# G1Tech-BME680_r1.net
KiCad netlist of a schematic drawn in EAGLE
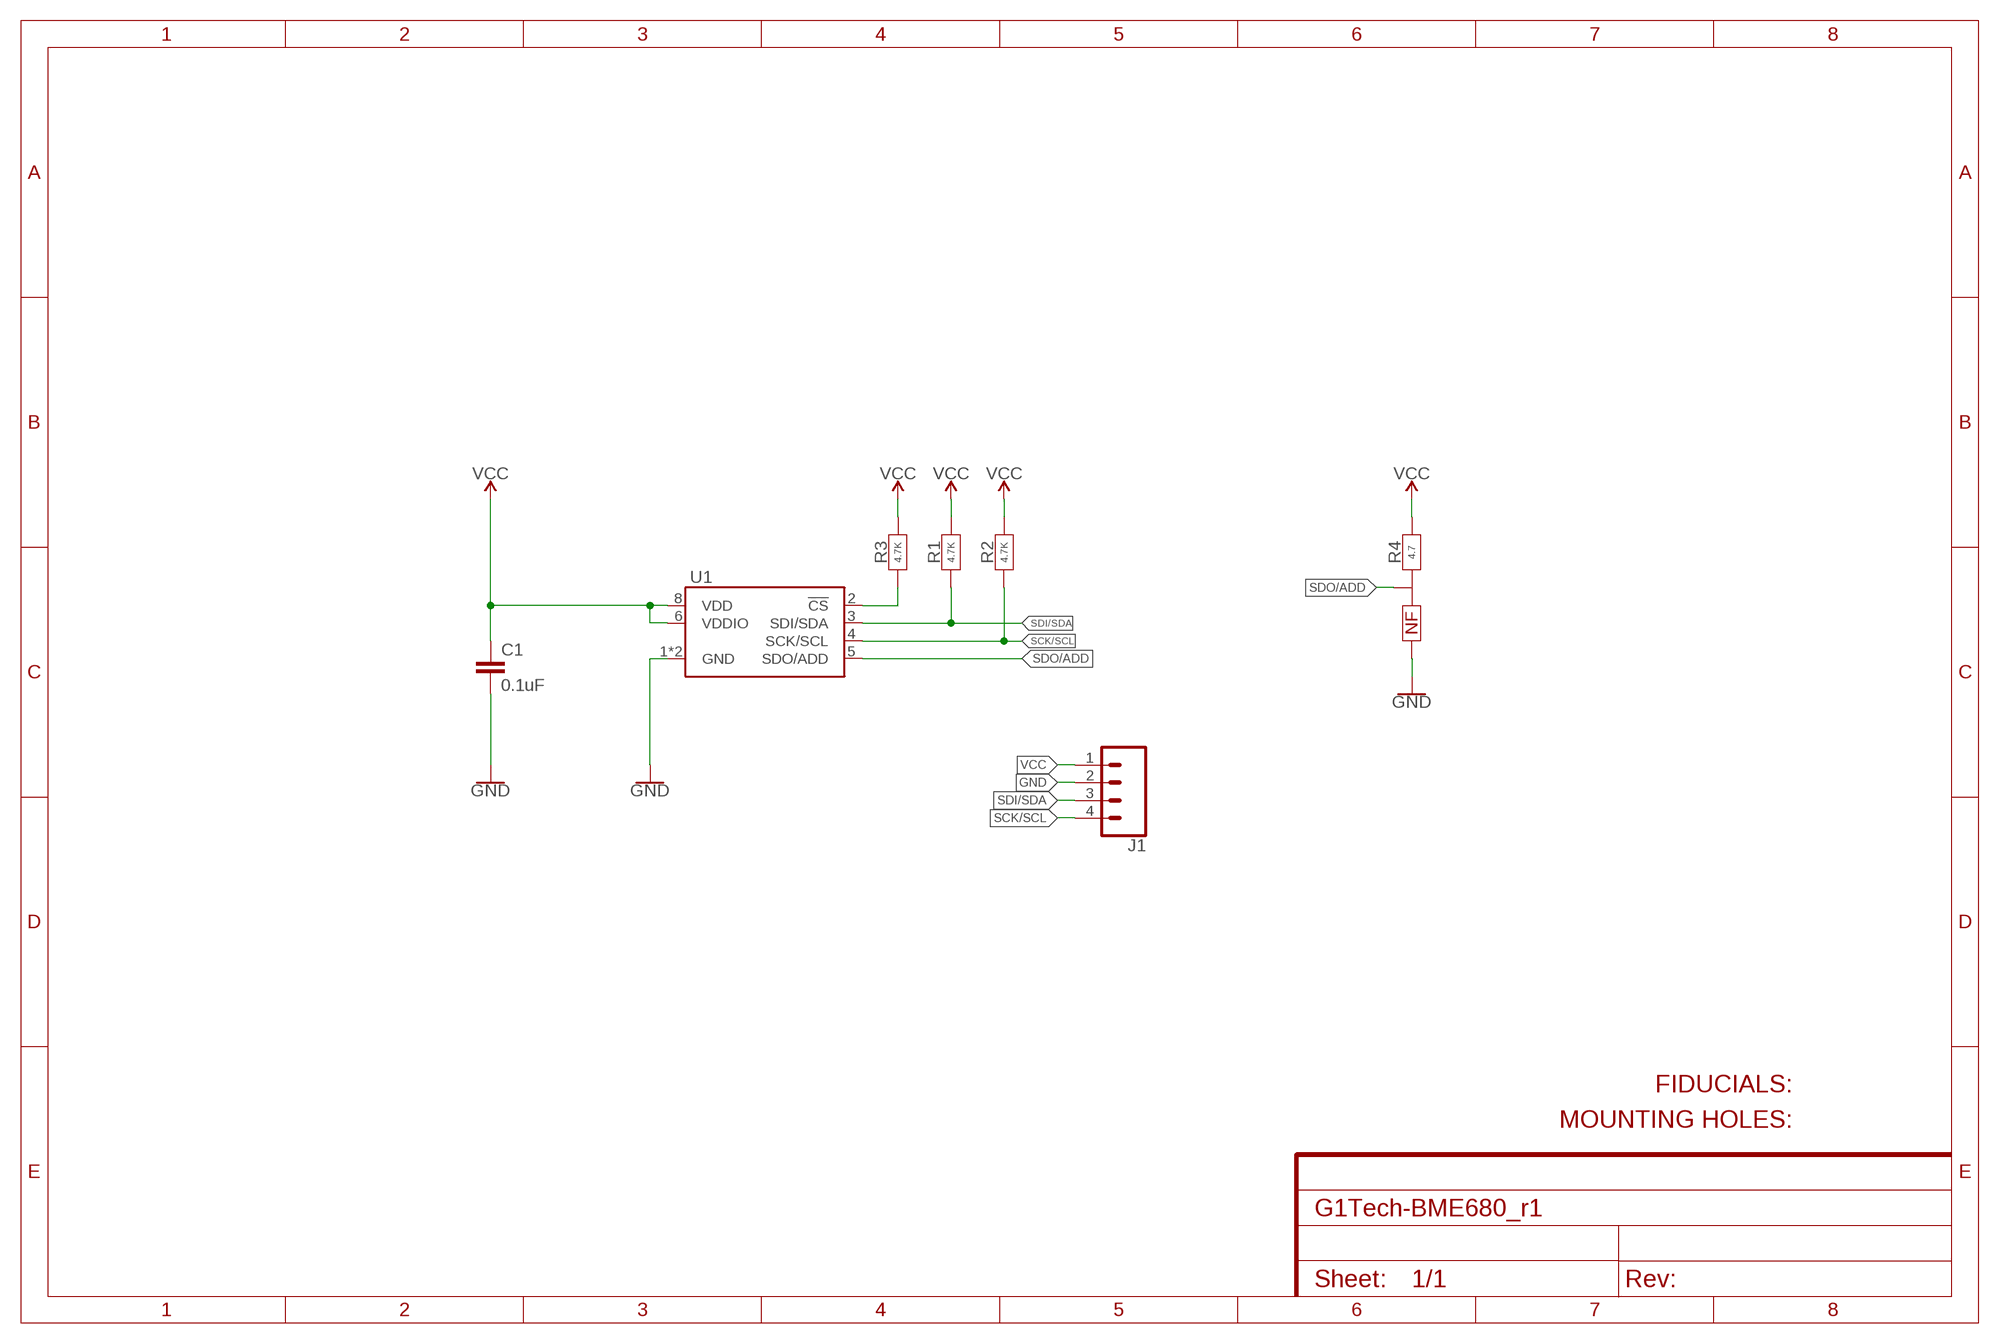
[diagram p0: schematic, sheet 1]

(export (version "E")
  (design (tool "Eeschema 10.0.6"))
  (components
    (comp (ref "C1")
      (value "0.1uF")
      (footprint "eagle-import:TDK-C0603")
      (libsource (lib "eagle-import") (part "TDK-C0603"))
    )
    (comp (ref "J1")
      (value "CONN_04")
      (footprint "eagle-import:1X04")
      (libsource (lib "eagle-import") (part "CONN_04"))
    )
    (comp (ref "R1")
      (value "4.7K")
      (footprint "eagle-import:YAGEO-R0603")
      (libsource (lib "eagle-import") (part "YAGEO-R0603"))
    )
    (comp (ref "R2")
      (value "4.7K")
      (footprint "eagle-import:YAGEO-R0603")
      (libsource (lib "eagle-import") (part "YAGEO-R0603"))
    )
    (comp (ref "R3")
      (value "4.7K")
      (footprint "eagle-import:YAGEO-R0603")
      (libsource (lib "eagle-import") (part "YAGEO-R0603"))
    )
    (comp (ref "R4")
      (value "4.7")
      (footprint "eagle-import:YAGEO-JP0603")
      (libsource (lib "eagle-import") (part "JUMPER-0R-UPJP0603-YAGEO"))
    )
    (comp (ref "U1")
      (value "BOSH-BME680")
      (footprint "eagle-import:BOSH-BME680")
      (libsource (lib "eagle-import") (part "BOSH-BME680"))
    )
  )
  (nets
    (net (code "1") (name "GND") (class "Default")
      (node (ref "C1") (pin "2") (pinfunction "2_2") (pintype "passive"))
      (node (ref "J1") (pin "2") (pinfunction "2_2") (pintype "passive"))
      (node (ref "R4") (pin "3") (pinfunction "3_3") (pintype "passive"))
      (node (ref "U1") (pin "1") (pinfunction "GND_1") (pintype "bidirectional"))
      (node (ref "U1") (pin "7") (pinfunction "GND_7") (pintype "bidirectional"))
    )
    (net (code "2") (name "Net-(U1-~{CS})") (class "Default")
      (node (ref "R3") (pin "1") (pinfunction "1_1") (pintype "passive"))
      (node (ref "U1") (pin "2") (pinfunction "~{CS}_2") (pintype "bidirectional"))
    )
    (net (code "3") (name "SCK{slash}SCL") (class "Default")
      (node (ref "J1") (pin "4") (pinfunction "4_4") (pintype "passive"))
      (node (ref "R2") (pin "1") (pinfunction "1_1") (pintype "passive"))
      (node (ref "U1") (pin "4") (pinfunction "SCK/SCL_4") (pintype "bidirectional"))
    )
    (net (code "4") (name "SDI{slash}SDA") (class "Default")
      (node (ref "J1") (pin "3") (pinfunction "3_3") (pintype "passive"))
      (node (ref "R1") (pin "1") (pinfunction "1_1") (pintype "passive"))
      (node (ref "U1") (pin "3") (pinfunction "SDI/SDA_3") (pintype "bidirectional"))
    )
    (net (code "5") (name "SDO{slash}ADD") (class "Default")
      (node (ref "R4") (pin "2") (pinfunction "2_2") (pintype "passive"))
      (node (ref "U1") (pin "5") (pinfunction "SDO/ADD_5") (pintype "bidirectional"))
    )
    (net (code "6") (name "VCC") (class "Default")
      (node (ref "C1") (pin "1") (pinfunction "1_1") (pintype "passive"))
      (node (ref "J1") (pin "1") (pinfunction "1_1") (pintype "passive"))
      (node (ref "R1") (pin "2") (pinfunction "2_2") (pintype "passive"))
      (node (ref "R2") (pin "2") (pinfunction "2_2") (pintype "passive"))
      (node (ref "R3") (pin "2") (pinfunction "2_2") (pintype "passive"))
      (node (ref "R4") (pin "1") (pinfunction "1_1") (pintype "passive"))
      (node (ref "U1") (pin "6") (pinfunction "VDDIO_6") (pintype "bidirectional"))
      (node (ref "U1") (pin "8") (pinfunction "VDD_8") (pintype "bidirectional"))
    )
  )
)
